# Adafruit_ESP32_Huzzah_Breakout.net
KiCad netlist of a schematic drawn in EAGLE
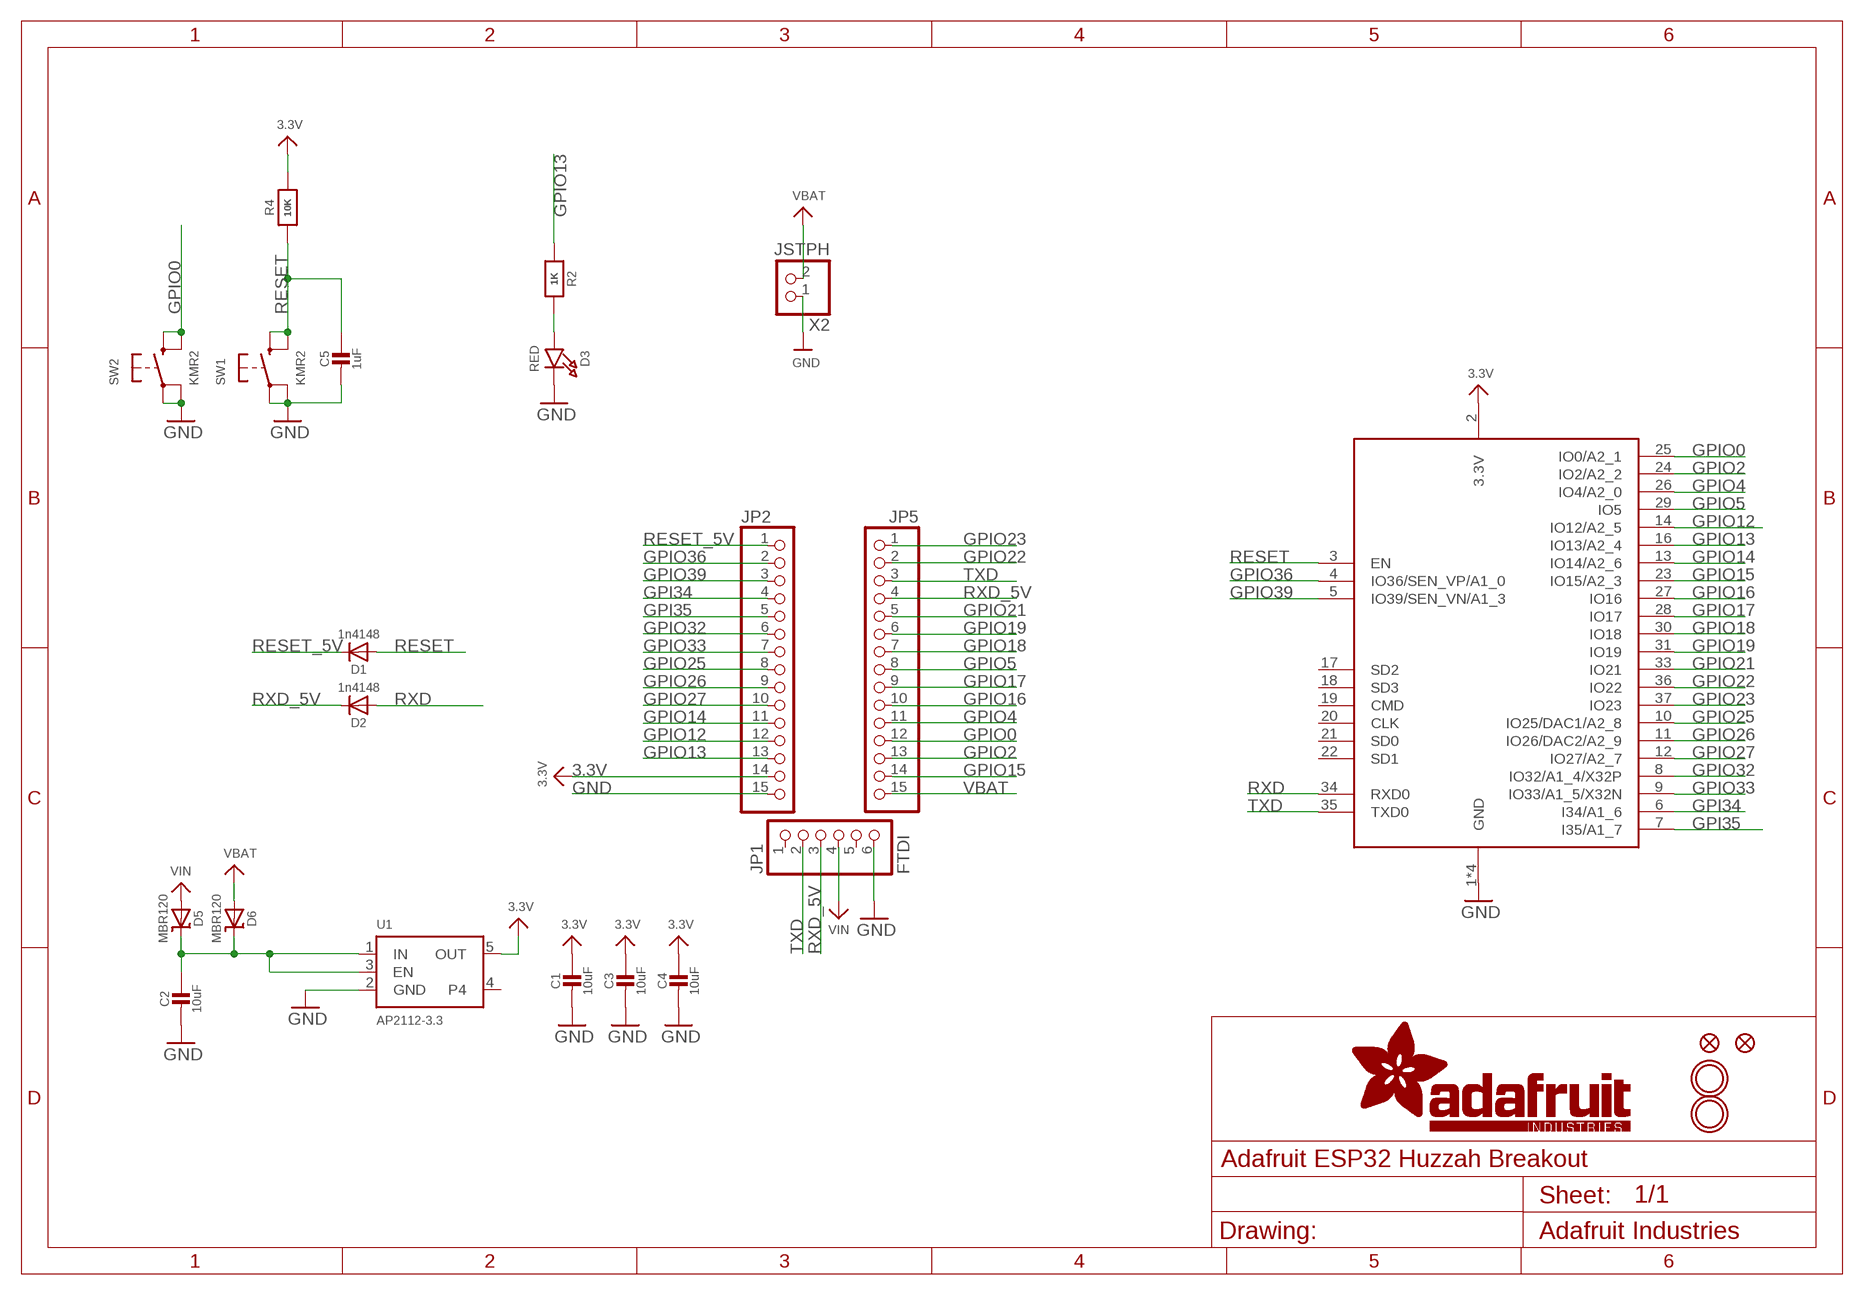
[diagram p0: schematic, sheet 1]

(export (version "E")
  (design (tool "Eeschema 10.0.6"))
  (components
    (comp (ref "C1")
      (value "10uF")
      (footprint "eagle-import:0805-NO")
      (libsource (lib "eagle-import") (part "CAP_CERAMIC0805-NOOUTLINE"))
    )
    (comp (ref "C2")
      (value "10uF")
      (footprint "eagle-import:0805-NO")
      (libsource (lib "eagle-import") (part "CAP_CERAMIC0805-NOOUTLINE"))
    )
    (comp (ref "C3")
      (value "10uF")
      (footprint "eagle-import:0805-NO")
      (libsource (lib "eagle-import") (part "CAP_CERAMIC0805-NOOUTLINE"))
    )
    (comp (ref "C4")
      (value "10uF")
      (footprint "eagle-import:0805-NO")
      (libsource (lib "eagle-import") (part "CAP_CERAMIC0805-NOOUTLINE"))
    )
    (comp (ref "C5")
      (value "1uF")
      (footprint "eagle-import:0805-NO")
      (libsource (lib "eagle-import") (part "CAP_CERAMIC0805-NOOUTLINE"))
    )
    (comp (ref "D1")
      (value "1n4148")
      (footprint "eagle-import:SOD-323")
      (libsource (lib "eagle-import") (part "DIODESOD-323"))
    )
    (comp (ref "D2")
      (value "1n4148")
      (footprint "eagle-import:SOD-323")
      (libsource (lib "eagle-import") (part "DIODESOD-323"))
    )
    (comp (ref "D3")
      (value "RED")
      (footprint "eagle-import:CHIPLED_0805_NOOUTLINE")
      (libsource (lib "eagle-import") (part "LED0805_NOOUTLINE"))
    )
    (comp (ref "D5")
      (value "MBR120")
      (footprint "eagle-import:SOD-123")
      (libsource (lib "eagle-import") (part "DIODE-SCHOTTKYSOD-123"))
    )
    (comp (ref "D6")
      (value "MBR120")
      (footprint "eagle-import:SOD-123")
      (libsource (lib "eagle-import") (part "DIODE-SCHOTTKYSOD-123"))
    )
    (comp (ref "FID1")
      (value "FIDUCIAL_1MM")
      (footprint "eagle-import:FIDUCIAL_1MM")
      (libsource (lib "eagle-import") (part "FIDUCIAL_1MM"))
    )
    (comp (ref "FID3")
      (value "FIDUCIAL_1MM")
      (footprint "eagle-import:FIDUCIAL_1MM")
      (libsource (lib "eagle-import") (part "FIDUCIAL_1MM"))
    )
    (comp (ref "JP1")
      (value "FTDI")
      (footprint "eagle-import:1X06_ROUND_70")
      (libsource (lib "eagle-import") (part "HEADER-1X670MIL"))
    )
    (comp (ref "JP2")
      (value "HEADER-1X15")
      (footprint "eagle-import:1X15_ROUND_70")
      (libsource (lib "eagle-import") (part "HEADER-1X15"))
    )
    (comp (ref "JP5")
      (value "HEADER-1X15")
      (footprint "eagle-import:1X15_ROUND_70")
      (libsource (lib "eagle-import") (part "HEADER-1X15"))
    )
    (comp (ref "R2")
      (value "1K")
      (footprint "eagle-import:0603-NO")
      (libsource (lib "eagle-import") (part "RESISTOR_0603_NOOUT"))
    )
    (comp (ref "R4")
      (value "10K")
      (footprint "eagle-import:0603-NO")
      (libsource (lib "eagle-import") (part "RESISTOR_0603_NOOUT"))
    )
    (comp (ref "SW1")
      (value "KMR2")
      (footprint "eagle-import:BTN_KMR2_4.6X2.8")
      (libsource (lib "eagle-import") (part "SWITCH_TACT_SMT4.6X2.8"))
    )
    (comp (ref "SW2")
      (value "KMR2")
      (footprint "eagle-import:BTN_KMR2_4.6X2.8")
      (libsource (lib "eagle-import") (part "SWITCH_TACT_SMT4.6X2.8"))
    )
    (comp (ref "U$15")
      (value "MOUNTINGHOLE2.5")
      (footprint "eagle-import:MOUNTINGHOLE_2.5_PLATED")
      (libsource (lib "eagle-import") (part "MOUNTINGHOLE2.5"))
    )
    (comp (ref "U$16")
      (value "MOUNTINGHOLE2.5")
      (footprint "eagle-import:MOUNTINGHOLE_2.5_PLATED")
      (libsource (lib "eagle-import") (part "MOUNTINGHOLE2.5"))
    )
    (comp (ref "U1")
      (value "AP2112-3.3")
      (footprint "eagle-import:SOT23-5")
      (libsource (lib "eagle-import") (part "VREG_SOT23-5"))
    )
    (comp (ref "X1")
      (value "ESP32_WROOM32")
      (footprint "eagle-import:WROOM32")
      (libsource (lib "eagle-import") (part "ESP32_WROOM32"))
    )
    (comp (ref "X2")
      (value "JSTPH")
      (footprint "eagle-import:JSTPH2")
      (libsource (lib "eagle-import") (part "CON_JST_PH_2PIN"))
    )
  )
  (nets
    (net (code "1") (name "/GPI34") (class "Default")
      (node (ref "JP2") (pin "4") (pinfunction "4_4") (pintype "passive"))
      (node (ref "X1") (pin "6") (pinfunction "I34/A1_6_6") (pintype "bidirectional"))
    )
    (net (code "2") (name "/GPI35") (class "Default")
      (node (ref "JP2") (pin "5") (pinfunction "5_5") (pintype "passive"))
      (node (ref "X1") (pin "7") (pinfunction "I35/A1_7_7") (pintype "bidirectional"))
    )
    (net (code "3") (name "/GPIO0") (class "Default")
      (node (ref "JP5") (pin "12") (pinfunction "12_12") (pintype "passive"))
      (node (ref "SW2") (pin "B") (pinfunction "S_B") (pintype "passive"))
      (node (ref "SW2") (pin "B'") (pinfunction "S1_B'") (pintype "passive"))
      (node (ref "X1") (pin "25") (pinfunction "IO0/A2_1_25") (pintype "bidirectional"))
    )
    (net (code "4") (name "/GPIO2") (class "Default")
      (node (ref "JP5") (pin "13") (pinfunction "13_13") (pintype "passive"))
      (node (ref "X1") (pin "24") (pinfunction "IO2/A2_2_24") (pintype "bidirectional"))
    )
    (net (code "5") (name "/GPIO4") (class "Default")
      (node (ref "JP5") (pin "11") (pinfunction "11_11") (pintype "passive"))
      (node (ref "X1") (pin "26") (pinfunction "IO4/A2_0_26") (pintype "bidirectional"))
    )
    (net (code "6") (name "/GPIO5") (class "Default")
      (node (ref "JP5") (pin "8") (pinfunction "8_8") (pintype "passive"))
      (node (ref "X1") (pin "29") (pinfunction "IO5_29") (pintype "bidirectional"))
    )
    (net (code "7") (name "/GPIO12") (class "Default")
      (node (ref "JP2") (pin "12") (pinfunction "12_12") (pintype "passive"))
      (node (ref "X1") (pin "14") (pinfunction "IO12/A2_5_14") (pintype "bidirectional"))
    )
    (net (code "8") (name "/GPIO13") (class "Default")
      (node (ref "JP2") (pin "13") (pinfunction "13_13") (pintype "passive"))
      (node (ref "R2") (pin "1") (pinfunction "1_1") (pintype "passive"))
      (node (ref "X1") (pin "16") (pinfunction "IO13/A2_4_16") (pintype "bidirectional"))
    )
    (net (code "9") (name "/GPIO14") (class "Default")
      (node (ref "JP2") (pin "11") (pinfunction "11_11") (pintype "passive"))
      (node (ref "X1") (pin "13") (pinfunction "IO14/A2_6_13") (pintype "bidirectional"))
    )
    (net (code "10") (name "/GPIO15") (class "Default")
      (node (ref "JP5") (pin "14") (pinfunction "14_14") (pintype "passive"))
      (node (ref "X1") (pin "23") (pinfunction "IO15/A2_3_23") (pintype "bidirectional"))
    )
    (net (code "11") (name "/GPIO16") (class "Default")
      (node (ref "JP5") (pin "10") (pinfunction "10_10") (pintype "passive"))
      (node (ref "X1") (pin "27") (pinfunction "IO16_27") (pintype "bidirectional"))
    )
    (net (code "12") (name "/GPIO17") (class "Default")
      (node (ref "JP5") (pin "9") (pinfunction "9_9") (pintype "passive"))
      (node (ref "X1") (pin "28") (pinfunction "IO17_28") (pintype "bidirectional"))
    )
    (net (code "13") (name "/GPIO18") (class "Default")
      (node (ref "JP5") (pin "7") (pinfunction "7_7") (pintype "passive"))
      (node (ref "X1") (pin "30") (pinfunction "IO18_30") (pintype "bidirectional"))
    )
    (net (code "14") (name "/GPIO19") (class "Default")
      (node (ref "JP5") (pin "6") (pinfunction "6_6") (pintype "passive"))
      (node (ref "X1") (pin "31") (pinfunction "IO19_31") (pintype "bidirectional"))
    )
    (net (code "15") (name "/GPIO21") (class "Default")
      (node (ref "JP5") (pin "5") (pinfunction "5_5") (pintype "passive"))
      (node (ref "X1") (pin "33") (pinfunction "IO21_33") (pintype "bidirectional"))
    )
    (net (code "16") (name "/GPIO22") (class "Default")
      (node (ref "JP5") (pin "2") (pinfunction "2_2") (pintype "passive"))
      (node (ref "X1") (pin "36") (pinfunction "IO22_36") (pintype "bidirectional"))
    )
    (net (code "17") (name "/GPIO23") (class "Default")
      (node (ref "JP5") (pin "1") (pinfunction "1_1") (pintype "passive"))
      (node (ref "X1") (pin "37") (pinfunction "IO23_37") (pintype "bidirectional"))
    )
    (net (code "18") (name "/GPIO25") (class "Default")
      (node (ref "JP2") (pin "8") (pinfunction "8_8") (pintype "passive"))
      (node (ref "X1") (pin "10") (pinfunction "IO25/DAC1/A2_8_10") (pintype "bidirectional"))
    )
    (net (code "19") (name "/GPIO26") (class "Default")
      (node (ref "JP2") (pin "9") (pinfunction "9_9") (pintype "passive"))
      (node (ref "X1") (pin "11") (pinfunction "IO26/DAC2/A2_9_11") (pintype "bidirectional"))
    )
    (net (code "20") (name "/GPIO27") (class "Default")
      (node (ref "JP2") (pin "10") (pinfunction "10_10") (pintype "passive"))
      (node (ref "X1") (pin "12") (pinfunction "IO27/A2_7_12") (pintype "bidirectional"))
    )
    (net (code "21") (name "/GPIO32") (class "Default")
      (node (ref "JP2") (pin "6") (pinfunction "6_6") (pintype "passive"))
      (node (ref "X1") (pin "8") (pinfunction "IO32/A1_4/X32P_8") (pintype "bidirectional"))
    )
    (net (code "22") (name "/GPIO33") (class "Default")
      (node (ref "JP2") (pin "7") (pinfunction "7_7") (pintype "passive"))
      (node (ref "X1") (pin "9") (pinfunction "IO33/A1_5/X32N_9") (pintype "bidirectional"))
    )
    (net (code "23") (name "/GPIO36") (class "Default")
      (node (ref "JP2") (pin "2") (pinfunction "2_2") (pintype "passive"))
      (node (ref "X1") (pin "4") (pinfunction "IO36/SEN_VP/A1_0_4") (pintype "passive"))
    )
    (net (code "24") (name "/GPIO39") (class "Default")
      (node (ref "JP2") (pin "3") (pinfunction "3_3") (pintype "passive"))
      (node (ref "X1") (pin "5") (pinfunction "IO39/SEN_VN/A1_3_5") (pintype "passive"))
    )
    (net (code "25") (name "/RESET") (class "Default")
      (node (ref "C5") (pin "1") (pinfunction "1_1") (pintype "passive"))
      (node (ref "D1") (pin "A") (pinfunction "A_A") (pintype "passive"))
      (node (ref "R4") (pin "1") (pinfunction "1_1") (pintype "passive"))
      (node (ref "SW1") (pin "B") (pinfunction "S_B") (pintype "passive"))
      (node (ref "SW1") (pin "B'") (pinfunction "S1_B'") (pintype "passive"))
      (node (ref "X1") (pin "3") (pinfunction "EN_3") (pintype "input"))
    )
    (net (code "26") (name "/RESET_5V") (class "Default")
      (node (ref "D1") (pin "C") (pinfunction "C_C") (pintype "passive"))
      (node (ref "JP2") (pin "1") (pinfunction "1_1") (pintype "passive"))
    )
    (net (code "27") (name "/RXD") (class "Default")
      (node (ref "D2") (pin "A") (pinfunction "A_A") (pintype "passive"))
      (node (ref "X1") (pin "34") (pinfunction "RXD0_34") (pintype "input"))
    )
    (net (code "28") (name "/RXD_5V") (class "Default")
      (node (ref "D2") (pin "C") (pinfunction "C_C") (pintype "passive"))
      (node (ref "JP1") (pin "3") (pinfunction "3_3") (pintype "passive"))
      (node (ref "JP5") (pin "4") (pinfunction "4_4") (pintype "passive"))
    )
    (net (code "29") (name "/TXD") (class "Default")
      (node (ref "JP1") (pin "2") (pinfunction "2_2") (pintype "passive"))
      (node (ref "JP5") (pin "3") (pinfunction "3_3") (pintype "passive"))
      (node (ref "X1") (pin "35") (pinfunction "TXD0_35") (pintype "output"))
    )
    (net (code "30") (name "3.3V") (class "Default")
      (node (ref "C1") (pin "1") (pinfunction "1_1") (pintype "passive"))
      (node (ref "C3") (pin "1") (pinfunction "1_1") (pintype "passive"))
      (node (ref "C4") (pin "1") (pinfunction "1_1") (pintype "passive"))
      (node (ref "JP2") (pin "14") (pinfunction "14_14") (pintype "passive"))
      (node (ref "R4") (pin "2") (pinfunction "2_2") (pintype "passive"))
      (node (ref "U1") (pin "5") (pinfunction "OUT_5") (pintype "power_in"))
      (node (ref "X1") (pin "2") (pinfunction "3.3V_2") (pintype "passive"))
    )
    (net (code "31") (name "GND") (class "Default")
      (node (ref "C1") (pin "2") (pinfunction "2_2") (pintype "passive"))
      (node (ref "C2") (pin "2") (pinfunction "2_2") (pintype "passive"))
      (node (ref "C3") (pin "2") (pinfunction "2_2") (pintype "passive"))
      (node (ref "C4") (pin "2") (pinfunction "2_2") (pintype "passive"))
      (node (ref "C5") (pin "2") (pinfunction "2_2") (pintype "passive"))
      (node (ref "D3") (pin "C") (pinfunction "C_C") (pintype "passive"))
      (node (ref "JP1") (pin "6") (pinfunction "6_6") (pintype "passive"))
      (node (ref "JP2") (pin "15") (pinfunction "15_15") (pintype "passive"))
      (node (ref "SW1") (pin "A") (pinfunction "P_A") (pintype "passive"))
      (node (ref "SW1") (pin "A'") (pinfunction "P1_A'") (pintype "passive"))
      (node (ref "SW2") (pin "A") (pinfunction "P_A") (pintype "passive"))
      (node (ref "SW2") (pin "A'") (pinfunction "P1_A'") (pintype "passive"))
      (node (ref "U1") (pin "2") (pinfunction "GND_2") (pintype "power_in"))
      (node (ref "X1") (pin "1") (pinfunction "GND_1") (pintype "passive"))
      (node (ref "X1") (pin "15") (pinfunction "GND_15") (pintype "passive"))
      (node (ref "X1") (pin "38") (pinfunction "GND_38") (pintype "passive"))
      (node (ref "X1") (pin "P$1") (pinfunction "GND_P$1") (pintype "passive"))
      (node (ref "X2") (pin "1") (pinfunction "1_1") (pintype "passive"))
    )
    (net (code "32") (name "Net-(D3-PadA)") (class "Default")
      (node (ref "D3") (pin "A") (pinfunction "A_A") (pintype "passive"))
      (node (ref "R2") (pin "2") (pinfunction "2_2") (pintype "passive"))
    )
    (net (code "33") (name "Net-(U1-EN)") (class "Default")
      (node (ref "C2") (pin "1") (pinfunction "1_1") (pintype "passive"))
      (node (ref "D5") (pin "C") (pinfunction "C_C") (pintype "passive"))
      (node (ref "D6") (pin "C") (pinfunction "C_C") (pintype "passive"))
      (node (ref "U1") (pin "1") (pinfunction "IN_1") (pintype "power_in"))
      (node (ref "U1") (pin "3") (pinfunction "EN_3") (pintype "input"))
    )
    (net (code "34") (name "VBAT") (class "Default")
      (node (ref "D6") (pin "A") (pinfunction "A_A") (pintype "passive"))
      (node (ref "JP5") (pin "15") (pinfunction "15_15") (pintype "passive"))
      (node (ref "X2") (pin "2") (pinfunction "2_2") (pintype "passive"))
    )
    (net (code "35") (name "VIN") (class "Default")
      (node (ref "D5") (pin "A") (pinfunction "A_A") (pintype "passive"))
      (node (ref "JP1") (pin "4") (pinfunction "4_4") (pintype "passive"))
    )
    (net (code "36") (name "unconnected-(JP1-Pad1)") (class "Default")
      (node (ref "JP1") (pin "1") (pinfunction "1_1") (pintype "passive"))
    )
    (net (code "37") (name "unconnected-(JP1-Pad5)") (class "Default")
      (node (ref "JP1") (pin "5") (pinfunction "5_5") (pintype "passive"))
    )
    (net (code "38") (name "unconnected-(U1-P4-Pad4)") (class "Default")
      (node (ref "U1") (pin "4") (pinfunction "P4_4") (pintype "bidirectional"))
    )
    (net (code "39") (name "unconnected-(X1-CLK-Pad20)") (class "Default")
      (node (ref "X1") (pin "20") (pinfunction "CLK_20") (pintype "bidirectional"))
    )
    (net (code "40") (name "unconnected-(X1-CMD-Pad19)") (class "Default")
      (node (ref "X1") (pin "19") (pinfunction "CMD_19") (pintype "bidirectional"))
    )
    (net (code "41") (name "unconnected-(X1-SD0-Pad21)") (class "Default")
      (node (ref "X1") (pin "21") (pinfunction "SD0_21") (pintype "bidirectional"))
    )
    (net (code "42") (name "unconnected-(X1-SD1-Pad22)") (class "Default")
      (node (ref "X1") (pin "22") (pinfunction "SD1_22") (pintype "bidirectional"))
    )
    (net (code "43") (name "unconnected-(X1-SD2-Pad17)") (class "Default")
      (node (ref "X1") (pin "17") (pinfunction "SD2_17") (pintype "bidirectional"))
    )
    (net (code "44") (name "unconnected-(X1-SD3-Pad18)") (class "Default")
      (node (ref "X1") (pin "18") (pinfunction "SD3_18") (pintype "bidirectional"))
    )
  )
)
